# anvil_debug_v2.net
KiCad netlist of a schematic drawn in EAGLE
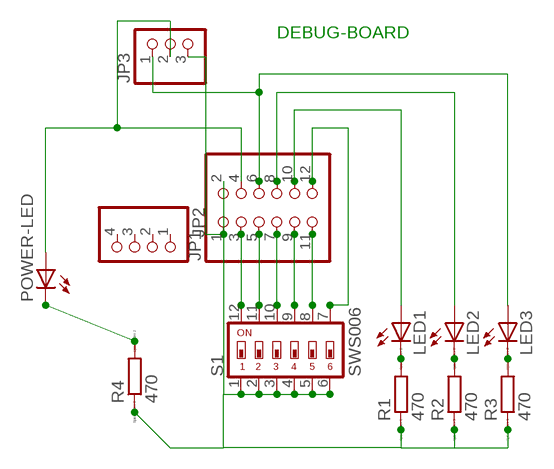
[diagram p0: schematic, sheet 1]

(export (version "E")
  (design (tool "Eeschema 10.0.6"))
  (components
    (comp (ref "JP1")
      (value "PINHD-2X6")
      (footprint "eagle-import:2X06")
      (libsource (lib "eagle-import") (part "PINHD-2X6"))
    )
    (comp (ref "JP2")
      (value "PINHD-1X4")
      (footprint "eagle-import:1X04")
      (libsource (lib "eagle-import") (part "PINHD-1X4"))
    )
    (comp (ref "JP3")
      (value "PINHD-1X3")
      (footprint "eagle-import:1X03")
      (libsource (lib "eagle-import") (part "PINHD-1X3"))
    )
    (comp (ref "LED1")
      (value "LEDSMT1206")
      (footprint "eagle-import:1206")
      (libsource (lib "eagle-import") (part "LEDSMT1206"))
    )
    (comp (ref "LED2")
      (value "LEDSMT1206")
      (footprint "eagle-import:1206")
      (libsource (lib "eagle-import") (part "LEDSMT1206"))
    )
    (comp (ref "LED3")
      (value "LEDSMT1206")
      (footprint "eagle-import:1206")
      (libsource (lib "eagle-import") (part "LEDSMT1206"))
    )
    (comp (ref "POWER-LED")
      (value "LEDSMT1206")
      (footprint "eagle-import:1206")
      (libsource (lib "eagle-import") (part "LEDSMT1206"))
    )
    (comp (ref "R1")
      (value "470")
      (footprint "eagle-import:R1206")
      (libsource (lib "eagle-import") (part "RR1206"))
    )
    (comp (ref "R2")
      (value "470")
      (footprint "eagle-import:R1206")
      (libsource (lib "eagle-import") (part "RR1206"))
    )
    (comp (ref "R3")
      (value "470")
      (footprint "eagle-import:R1206")
      (libsource (lib "eagle-import") (part "RR1206"))
    )
    (comp (ref "R4")
      (value "470")
      (footprint "eagle-import:R1206")
      (libsource (lib "eagle-import") (part "RR1206"))
    )
    (comp (ref "S1")
      (value "SWS006")
      (footprint "eagle-import:SMS-006")
      (libsource (lib "eagle-import") (part "SWS006"))
    )
  )
  (nets
    (net (code "1") (name "Net-(JP1-Pad1)") (class "Default")
      (node (ref "JP1") (pin "1") (pinfunction "1_1") (pintype "passive"))
      (node (ref "JP1") (pin "2") (pinfunction "2_2") (pintype "passive"))
      (node (ref "JP3") (pin "3") (pinfunction "3_3") (pintype "passive"))
      (node (ref "R1") (pin "1") (pinfunction "1_1") (pintype "passive"))
      (node (ref "R2") (pin "1") (pinfunction "1_1") (pintype "passive"))
      (node (ref "R3") (pin "1") (pinfunction "1_1") (pintype "passive"))
      (node (ref "R4") (pin "1") (pinfunction "1_1") (pintype "passive"))
      (node (ref "S1") (pin "1") (pinfunction "1_1") (pintype "passive"))
      (node (ref "S1") (pin "2") (pinfunction "2_2") (pintype "passive"))
      (node (ref "S1") (pin "3") (pinfunction "3_3") (pintype "passive"))
      (node (ref "S1") (pin "4") (pinfunction "4_4") (pintype "passive"))
      (node (ref "S1") (pin "5") (pinfunction "5_5") (pintype "passive"))
      (node (ref "S1") (pin "6") (pinfunction "6_6") (pintype "passive"))
    )
    (net (code "2") (name "Net-(JP1-Pad3)") (class "Default")
      (node (ref "JP1") (pin "3") (pinfunction "3_3") (pintype "passive"))
      (node (ref "S1") (pin "12") (pinfunction "12_12") (pintype "passive"))
    )
    (net (code "3") (name "Net-(JP1-Pad4)") (class "Default")
      (node (ref "JP1") (pin "4") (pinfunction "4_4") (pintype "passive"))
      (node (ref "JP3") (pin "2") (pinfunction "2_2") (pintype "passive"))
      (node (ref "POWER-LED") (pin "A") (pinfunction "A_A") (pintype "passive"))
    )
    (net (code "4") (name "Net-(JP1-Pad5)") (class "Default")
      (node (ref "JP1") (pin "5") (pinfunction "5_5") (pintype "passive"))
      (node (ref "S1") (pin "11") (pinfunction "11_11") (pintype "passive"))
    )
    (net (code "5") (name "Net-(JP1-Pad6)") (class "Default")
      (node (ref "JP1") (pin "6") (pinfunction "6_6") (pintype "passive"))
      (node (ref "JP3") (pin "1") (pinfunction "1_1") (pintype "passive"))
      (node (ref "LED3") (pin "A") (pinfunction "A_A") (pintype "passive"))
    )
    (net (code "6") (name "Net-(JP1-Pad7)") (class "Default")
      (node (ref "JP1") (pin "7") (pinfunction "7_7") (pintype "passive"))
      (node (ref "S1") (pin "10") (pinfunction "10_10") (pintype "passive"))
    )
    (net (code "7") (name "Net-(JP1-Pad8)") (class "Default")
      (node (ref "JP1") (pin "8") (pinfunction "8_8") (pintype "passive"))
      (node (ref "LED2") (pin "A") (pinfunction "A_A") (pintype "passive"))
    )
    (net (code "8") (name "Net-(JP1-Pad9)") (class "Default")
      (node (ref "JP1") (pin "9") (pinfunction "9_9") (pintype "passive"))
      (node (ref "S1") (pin "9") (pinfunction "9_9") (pintype "passive"))
    )
    (net (code "9") (name "Net-(JP1-Pad10)") (class "Default")
      (node (ref "JP1") (pin "10") (pinfunction "10_10") (pintype "passive"))
      (node (ref "LED1") (pin "A") (pinfunction "A_A") (pintype "passive"))
    )
    (net (code "10") (name "Net-(JP1-Pad11)") (class "Default")
      (node (ref "JP1") (pin "11") (pinfunction "11_11") (pintype "passive"))
      (node (ref "S1") (pin "8") (pinfunction "8_8") (pintype "passive"))
    )
    (net (code "11") (name "Net-(JP1-Pad12)") (class "Default")
      (node (ref "JP1") (pin "12") (pinfunction "12_12") (pintype "passive"))
      (node (ref "S1") (pin "7") (pinfunction "7_7") (pintype "passive"))
    )
    (net (code "12") (name "Net-(LED1-PadC)") (class "Default")
      (node (ref "LED1") (pin "C") (pinfunction "C_C") (pintype "passive"))
      (node (ref "R1") (pin "2") (pinfunction "2_2") (pintype "passive"))
    )
    (net (code "13") (name "Net-(LED2-PadC)") (class "Default")
      (node (ref "LED2") (pin "C") (pinfunction "C_C") (pintype "passive"))
      (node (ref "R2") (pin "2") (pinfunction "2_2") (pintype "passive"))
    )
    (net (code "14") (name "Net-(LED3-PadC)") (class "Default")
      (node (ref "LED3") (pin "C") (pinfunction "C_C") (pintype "passive"))
      (node (ref "R3") (pin "2") (pinfunction "2_2") (pintype "passive"))
    )
    (net (code "15") (name "Net-(POWER-LED-PadC)") (class "Default")
      (node (ref "POWER-LED") (pin "C") (pinfunction "C_C") (pintype "passive"))
      (node (ref "R4") (pin "2") (pinfunction "2_2") (pintype "passive"))
    )
    (net (code "16") (name "unconnected-(JP2-Pad1)") (class "Default")
      (node (ref "JP2") (pin "1") (pinfunction "1_1") (pintype "passive"))
    )
    (net (code "17") (name "unconnected-(JP2-Pad2)") (class "Default")
      (node (ref "JP2") (pin "2") (pinfunction "2_2") (pintype "passive"))
    )
    (net (code "18") (name "unconnected-(JP2-Pad3)") (class "Default")
      (node (ref "JP2") (pin "3") (pinfunction "3_3") (pintype "passive"))
    )
    (net (code "19") (name "unconnected-(JP2-Pad4)") (class "Default")
      (node (ref "JP2") (pin "4") (pinfunction "4_4") (pintype "passive"))
    )
  )
)
